# Encoder.net
KiCad netlist of a schematic drawn in EAGLE
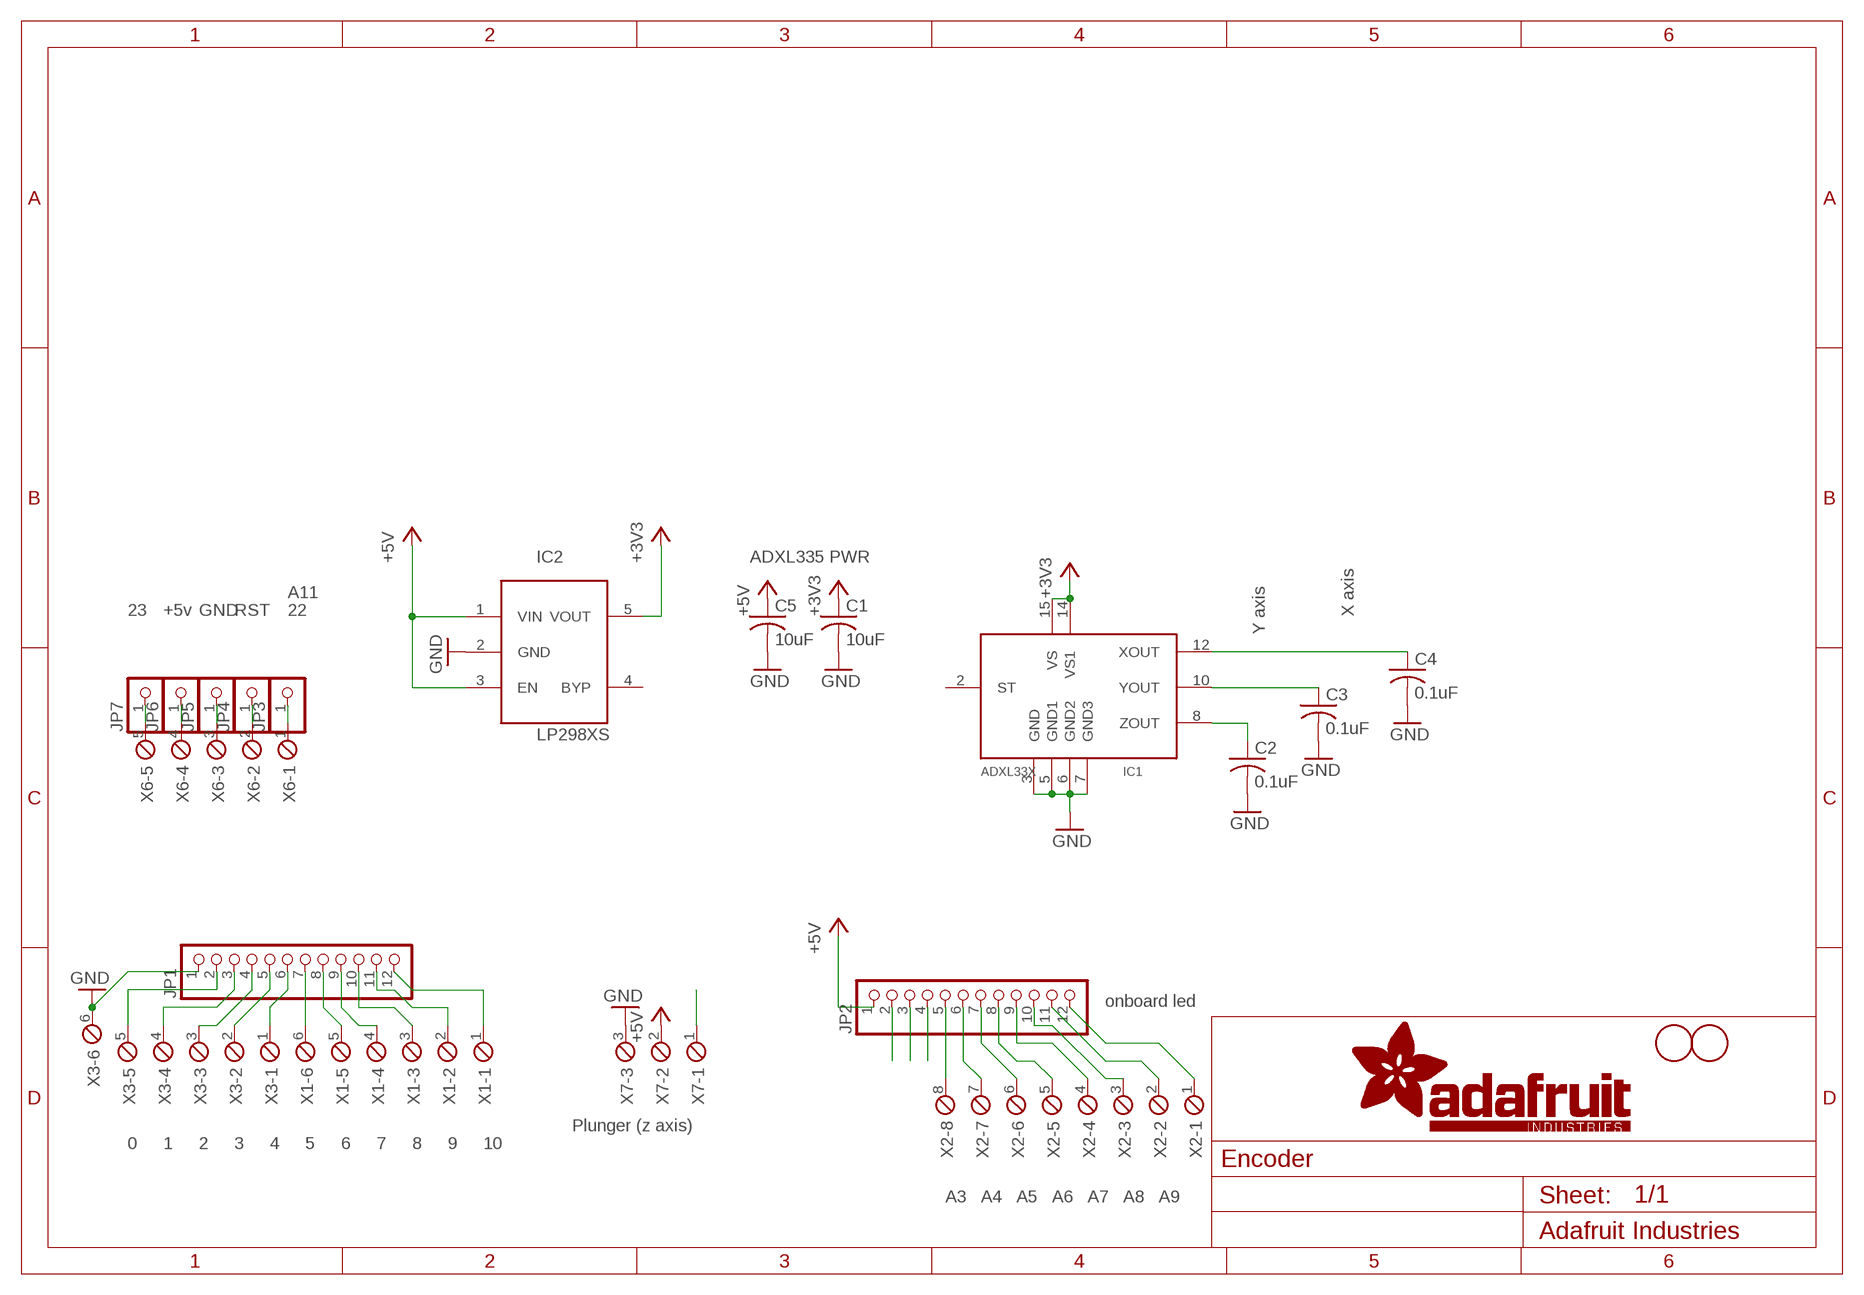
[diagram p0: schematic, sheet 1]

(export (version "E")
  (design (tool "Eeschema 10.0.6"))
  (components
    (comp (ref "C1")
      (value "10uF")
      (footprint "eagle-import:C0805K")
      (libsource (lib "eagle-import") (part "C-USC0805K"))
    )
    (comp (ref "C2")
      (value "0.1uF")
      (footprint "eagle-import:C0805K")
      (libsource (lib "eagle-import") (part "C-USC0805K"))
    )
    (comp (ref "C3")
      (value "0.1uF")
      (footprint "eagle-import:C0805K")
      (libsource (lib "eagle-import") (part "C-USC0805K"))
    )
    (comp (ref "C4")
      (value "0.1uF")
      (footprint "eagle-import:C0805K")
      (libsource (lib "eagle-import") (part "C-USC0805K"))
    )
    (comp (ref "C5")
      (value "10uF")
      (footprint "eagle-import:C0805K")
      (libsource (lib "eagle-import") (part "C-USC0805K"))
    )
    (comp (ref "IC1")
      (value "ADXL33X")
      (footprint "eagle-import:16LCSP")
      (libsource (lib "eagle-import") (part "ADXL33X"))
    )
    (comp (ref "IC2")
      (value "LP298XS")
      (footprint "eagle-import:SOT23-5L")
      (libsource (lib "eagle-import") (part "LP298XS"))
    )
    (comp (ref "JP1")
      (value "PINHD-1X12-CB")
      (footprint "eagle-import:1X12-CB")
      (libsource (lib "eagle-import") (part "PINHD-1X12-CB"))
    )
    (comp (ref "JP2")
      (value "PINHD-1X12-CB")
      (footprint "eagle-import:1X12-CB")
      (libsource (lib "eagle-import") (part "PINHD-1X12-CB"))
    )
    (comp (ref "JP3")
      (value "PINHD-1X1CB")
      (footprint "eagle-import:1X01-CLEANBIG")
      (libsource (lib "eagle-import") (part "PINHD-1X1CB"))
    )
    (comp (ref "JP4")
      (value "PINHD-1X1CB")
      (footprint "eagle-import:1X01-CLEANBIG")
      (libsource (lib "eagle-import") (part "PINHD-1X1CB"))
    )
    (comp (ref "JP5")
      (value "PINHD-1X1CB")
      (footprint "eagle-import:1X01-CLEANBIG")
      (libsource (lib "eagle-import") (part "PINHD-1X1CB"))
    )
    (comp (ref "JP6")
      (value "PINHD-1X1CB")
      (footprint "eagle-import:1X01-CLEANBIG")
      (libsource (lib "eagle-import") (part "PINHD-1X1CB"))
    )
    (comp (ref "JP7")
      (value "PINHD-1X1CB")
      (footprint "eagle-import:1X01-CLEANBIG")
      (libsource (lib "eagle-import") (part "PINHD-1X1CB"))
    )
    (comp (ref "U$1")
      (value "FIDUCIAL")
      (footprint "eagle-import:FIDUCIAL_1MM")
      (libsource (lib "eagle-import") (part "FIDUCIAL"))
    )
    (comp (ref "U$2")
      (value "FIDUCIAL")
      (footprint "eagle-import:FIDUCIAL_1MM")
      (libsource (lib "eagle-import") (part "FIDUCIAL"))
    )
    (comp (ref "X1")
      (value "MPT6")
      (footprint "eagle-import:6POL254")
      (libsource (lib "eagle-import") (part "MPT6"))
    )
    (comp (ref "X2")
      (value "MPT8")
      (footprint "eagle-import:8POL254")
      (libsource (lib "eagle-import") (part "MPT8"))
    )
    (comp (ref "X3")
      (value "MPT6")
      (footprint "eagle-import:6POL254")
      (libsource (lib "eagle-import") (part "MPT6"))
    )
    (comp (ref "X6")
      (value "MPT5")
      (footprint "eagle-import:5POL254")
      (libsource (lib "eagle-import") (part "MPT5"))
    )
    (comp (ref "X7")
      (value "MPT3")
      (footprint "eagle-import:3POL254")
      (libsource (lib "eagle-import") (part "MPT3"))
    )
  )
  (nets
    (net (code "1") (name "+3V3") (class "Default")
      (node (ref "C1") (pin "1") (pinfunction "1_1") (pintype "passive"))
      (node (ref "IC1") (pin "14") (pinfunction "VS1_14") (pintype "power_in"))
      (node (ref "IC1") (pin "15") (pinfunction "VS_15") (pintype "power_in"))
      (node (ref "IC2") (pin "5") (pinfunction "VOUT_5") (pintype "bidirectional"))
    )
    (net (code "2") (name "+5V") (class "Default")
      (node (ref "C5") (pin "1") (pinfunction "1_1") (pintype "passive"))
      (node (ref "IC2") (pin "1") (pinfunction "VIN_1") (pintype "bidirectional"))
      (node (ref "IC2") (pin "3") (pinfunction "EN_3") (pintype "bidirectional"))
      (node (ref "JP2") (pin "1") (pinfunction "1_1") (pintype "passive"))
      (node (ref "X7") (pin "2") (pinfunction "1_2") (pintype "passive"))
    )
    (net (code "3") (name "/XOUT") (class "Default")
      (node (ref "C4") (pin "1") (pinfunction "1_1") (pintype "passive"))
      (node (ref "IC1") (pin "12") (pinfunction "XOUT_12") (pintype "output"))
      (node (ref "JP2") (pin "2") (pinfunction "2_2") (pintype "passive"))
    )
    (net (code "4") (name "/YOUT") (class "Default")
      (node (ref "C3") (pin "1") (pinfunction "1_1") (pintype "passive"))
      (node (ref "IC1") (pin "10") (pinfunction "YOUT_10") (pintype "output"))
      (node (ref "JP2") (pin "3") (pinfunction "3_3") (pintype "passive"))
    )
    (net (code "5") (name "/ZIN") (class "Default")
      (node (ref "JP2") (pin "4") (pinfunction "4_4") (pintype "passive"))
      (node (ref "X7") (pin "1") (pinfunction "1_1") (pintype "passive"))
    )
    (net (code "6") (name "GND") (class "Default")
      (node (ref "C1") (pin "2") (pinfunction "2_2") (pintype "passive"))
      (node (ref "C2") (pin "2") (pinfunction "2_2") (pintype "passive"))
      (node (ref "C3") (pin "2") (pinfunction "2_2") (pintype "passive"))
      (node (ref "C4") (pin "2") (pinfunction "2_2") (pintype "passive"))
      (node (ref "C5") (pin "2") (pinfunction "2_2") (pintype "passive"))
      (node (ref "IC1") (pin "3") (pinfunction "GND_3") (pintype "power_in"))
      (node (ref "IC1") (pin "5") (pinfunction "GND1_5") (pintype "power_in"))
      (node (ref "IC1") (pin "6") (pinfunction "GND2_6") (pintype "power_in"))
      (node (ref "IC1") (pin "7") (pinfunction "GND3_7") (pintype "power_in"))
      (node (ref "IC2") (pin "2") (pinfunction "GND_2") (pintype "bidirectional"))
      (node (ref "JP1") (pin "1") (pinfunction "1_1") (pintype "passive"))
      (node (ref "X3") (pin "6") (pinfunction "1_6") (pintype "passive"))
      (node (ref "X7") (pin "3") (pinfunction "1_3") (pintype "passive"))
    )
    (net (code "7") (name "Net-(IC1-ZOUT)") (class "Default")
      (node (ref "C2") (pin "1") (pinfunction "1_1") (pintype "passive"))
      (node (ref "IC1") (pin "8") (pinfunction "ZOUT_8") (pintype "output"))
    )
    (net (code "8") (name "Net-(JP1-Pad6)") (class "Default")
      (node (ref "JP1") (pin "6") (pinfunction "6_6") (pintype "passive"))
      (node (ref "X3") (pin "1") (pinfunction "1_1") (pintype "passive"))
    )
    (net (code "9") (name "Net-(JP1-Pad12)") (class "Default")
      (node (ref "JP1") (pin "12") (pinfunction "12_12") (pintype "passive"))
      (node (ref "X1") (pin "1") (pinfunction "1_1") (pintype "passive"))
    )
    (net (code "10") (name "Net-(JP2-Pad12)") (class "Default")
      (node (ref "JP2") (pin "12") (pinfunction "12_12") (pintype "passive"))
      (node (ref "X2") (pin "1") (pinfunction "1_1") (pintype "passive"))
    )
    (net (code "11") (name "Net-(JP3-Pad1)") (class "Default")
      (node (ref "JP3") (pin "1") (pinfunction "1_1") (pintype "passive"))
      (node (ref "X6") (pin "1") (pinfunction "1_1") (pintype "passive"))
    )
    (net (code "12") (name "Net-(X1B-1)") (class "Default")
      (node (ref "JP1") (pin "11") (pinfunction "11_11") (pintype "passive"))
      (node (ref "X1") (pin "2") (pinfunction "1_2") (pintype "passive"))
    )
    (net (code "13") (name "Net-(X1C-1)") (class "Default")
      (node (ref "JP1") (pin "10") (pinfunction "10_10") (pintype "passive"))
      (node (ref "X1") (pin "3") (pinfunction "1_3") (pintype "passive"))
    )
    (net (code "14") (name "Net-(X1D-1)") (class "Default")
      (node (ref "JP1") (pin "9") (pinfunction "9_9") (pintype "passive"))
      (node (ref "X1") (pin "4") (pinfunction "1_4") (pintype "passive"))
    )
    (net (code "15") (name "Net-(X1E-1)") (class "Default")
      (node (ref "JP1") (pin "8") (pinfunction "8_8") (pintype "passive"))
      (node (ref "X1") (pin "5") (pinfunction "1_5") (pintype "passive"))
    )
    (net (code "16") (name "Net-(X1F-1)") (class "Default")
      (node (ref "JP1") (pin "7") (pinfunction "7_7") (pintype "passive"))
      (node (ref "X1") (pin "6") (pinfunction "1_6") (pintype "passive"))
    )
    (net (code "17") (name "Net-(X2B-1)") (class "Default")
      (node (ref "JP2") (pin "11") (pinfunction "11_11") (pintype "passive"))
      (node (ref "X2") (pin "2") (pinfunction "1_2") (pintype "passive"))
    )
    (net (code "18") (name "Net-(X2C-1)") (class "Default")
      (node (ref "JP2") (pin "10") (pinfunction "10_10") (pintype "passive"))
      (node (ref "X2") (pin "3") (pinfunction "1_3") (pintype "passive"))
    )
    (net (code "19") (name "Net-(X2D-1)") (class "Default")
      (node (ref "JP2") (pin "9") (pinfunction "9_9") (pintype "passive"))
      (node (ref "X2") (pin "4") (pinfunction "1_4") (pintype "passive"))
    )
    (net (code "20") (name "Net-(X2E-1)") (class "Default")
      (node (ref "JP2") (pin "8") (pinfunction "8_8") (pintype "passive"))
      (node (ref "X2") (pin "5") (pinfunction "1_5") (pintype "passive"))
    )
    (net (code "21") (name "Net-(X2F-1)") (class "Default")
      (node (ref "JP2") (pin "7") (pinfunction "7_7") (pintype "passive"))
      (node (ref "X2") (pin "6") (pinfunction "1_6") (pintype "passive"))
    )
    (net (code "22") (name "Net-(X2G-1)") (class "Default")
      (node (ref "JP2") (pin "6") (pinfunction "6_6") (pintype "passive"))
      (node (ref "X2") (pin "7") (pinfunction "1_7") (pintype "passive"))
    )
    (net (code "23") (name "Net-(X2H-1)") (class "Default")
      (node (ref "JP2") (pin "5") (pinfunction "5_5") (pintype "passive"))
      (node (ref "X2") (pin "8") (pinfunction "1_8") (pintype "passive"))
    )
    (net (code "24") (name "Net-(X3B-1)") (class "Default")
      (node (ref "JP1") (pin "5") (pinfunction "5_5") (pintype "passive"))
      (node (ref "X3") (pin "2") (pinfunction "1_2") (pintype "passive"))
    )
    (net (code "25") (name "Net-(X3C-1)") (class "Default")
      (node (ref "JP1") (pin "4") (pinfunction "4_4") (pintype "passive"))
      (node (ref "X3") (pin "3") (pinfunction "1_3") (pintype "passive"))
    )
    (net (code "26") (name "Net-(X3D-1)") (class "Default")
      (node (ref "JP1") (pin "3") (pinfunction "3_3") (pintype "passive"))
      (node (ref "X3") (pin "4") (pinfunction "1_4") (pintype "passive"))
    )
    (net (code "27") (name "Net-(X3E-1)") (class "Default")
      (node (ref "JP1") (pin "2") (pinfunction "2_2") (pintype "passive"))
      (node (ref "X3") (pin "5") (pinfunction "1_5") (pintype "passive"))
    )
    (net (code "28") (name "Net-(X6B-1)") (class "Default")
      (node (ref "JP4") (pin "1") (pinfunction "1_1") (pintype "passive"))
      (node (ref "X6") (pin "2") (pinfunction "1_2") (pintype "passive"))
    )
    (net (code "29") (name "Net-(X6C-1)") (class "Default")
      (node (ref "JP5") (pin "1") (pinfunction "1_1") (pintype "passive"))
      (node (ref "X6") (pin "3") (pinfunction "1_3") (pintype "passive"))
    )
    (net (code "30") (name "Net-(X6D-1)") (class "Default")
      (node (ref "JP6") (pin "1") (pinfunction "1_1") (pintype "passive"))
      (node (ref "X6") (pin "4") (pinfunction "1_4") (pintype "passive"))
    )
    (net (code "31") (name "Net-(X6E-1)") (class "Default")
      (node (ref "JP7") (pin "1") (pinfunction "1_1") (pintype "passive"))
      (node (ref "X6") (pin "5") (pinfunction "1_5") (pintype "passive"))
    )
    (net (code "32") (name "unconnected-(IC1-ST-Pad2)") (class "Default")
      (node (ref "IC1") (pin "2") (pinfunction "ST_2") (pintype "input"))
    )
    (net (code "33") (name "unconnected-(IC2-BYP-Pad4)") (class "Default")
      (node (ref "IC2") (pin "4") (pinfunction "BYP_4") (pintype "bidirectional"))
    )
  )
)
